# STM32F103C8T6_Core.net
KiCad netlist of a schematic drawn in Altium Designer
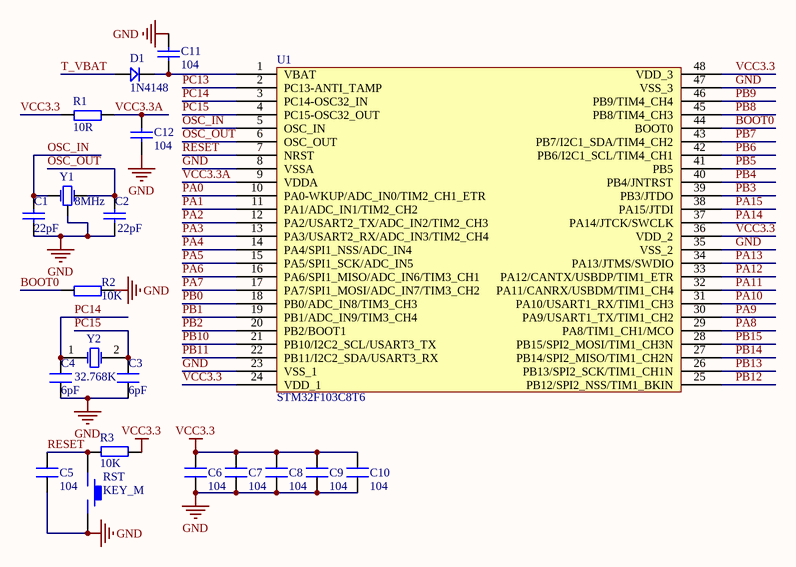
[diagram p0: STM32F103C8T6_Core.SchDoc]

(export (version "E")
  (design (tool "Eeschema 10.0.6"))
  (components
    (comp (ref "C1") (value "22pF") (footprint "C 0603_M") (libsource (lib "L476") (part "CAP")))
    (comp (ref "C2") (value "22pF") (footprint "C 0603_M") (libsource (lib "L476") (part "CAP")))
    (comp (ref "C3")
      (value "6pF")
      (footprint "C 0603_M")
      (libsource (lib "WarShip V3 STM32103封装库") (part "C"))
    )
    (comp (ref "C4")
      (value "6pF")
      (footprint "C 0603_M")
      (libsource (lib "WarShip V3 STM32103封装库") (part "C"))
    )
    (comp (ref "C5")
      (value "104")
      (footprint "C 0603_M")
      (libsource (lib "WarShip V3 STM32103封装库") (part "C"))
    )
    (comp (ref "C6")
      (value "104")
      (footprint "C 0603_M")
      (libsource (lib "WarShip V3 STM32103封装库") (part "C"))
    )
    (comp (ref "C7")
      (value "104")
      (footprint "C 0603_M")
      (libsource (lib "WarShip V3 STM32103封装库") (part "C"))
    )
    (comp (ref "C8")
      (value "104")
      (footprint "C 0603_M")
      (libsource (lib "WarShip V3 STM32103封装库") (part "C"))
    )
    (comp (ref "C9")
      (value "104")
      (footprint "C 0603_M")
      (libsource (lib "WarShip V3 STM32103封装库") (part "C"))
    )
    (comp (ref "C10")
      (value "104")
      (footprint "C 0603_M")
      (libsource (lib "WarShip V3 STM32103封装库") (part "C"))
    )
    (comp (ref "C11") (value "104") (footprint "C 0603_M") (libsource (lib "L476") (part "CAP")))
    (comp (ref "C12") (value "104") (footprint "C 0603_M") (libsource (lib "L476") (part "CAP")))
    (comp (ref "D1")
      (value "1N4148")
      (footprint "DIODE_SOP")
      (libsource (lib "阿波罗STM32F4&F7底板封装库") (part "D"))
    )
    (comp (ref "R1")
      (value "10R")
      (footprint "R 0603_M")
      (libsource (lib "WarShip V3 STM32103封装库") (part "R"))
    )
    (comp (ref "R2")
      (value "10K")
      (footprint "R 0603_M")
      (libsource (lib "WarShip V3 STM32103封装库") (part "R"))
    )
    (comp (ref "R3")
      (value "10K")
      (footprint "R 0603_M")
      (libsource (lib "WarShip V3 STM32103封装库") (part "R"))
    )
    (comp (ref "RST")
      (value "KEY_M")
      (footprint "TSW SMD-3*6*2.5")
      (libsource (lib "STM32F429核心板封装库") (part "KEY_M"))
    )
    (comp (ref "U1")
      (value "STM32F103C8T6")
      (footprint "LQFP-48PIN")
      (libsource (lib "Pandora_STM32L4_Board_V2.4") (part "U-STM32F103C8T6"))
    )
    (comp (ref "Y1")
      (value "8MHz")
      (footprint "Y-XTAL-3215-3P")
      (description "XTAL,3215,8MHz")
      (libsource (lib "Pandora_STM32L4_Board_V2.4") (part "Y-3215-8M"))
    )
    (comp (ref "Y2")
      (value "32.768K")
      (footprint "OSC 3215-2P")
      (description "Crystal Oscillator")
      (fields (field (name "PUBLISHER") "Altium Limited"))
      (libsource (lib "WarShip V3 STM32103封装库") (part "XTAL"))
    )
  )
  (nets
    (net (code "1") (name "/BOOT0") (class "Default")
      (node (ref "R2") (pin "1") (pintype "passive"))
      (node (ref "U1") (pin "44") (pinfunction "BOOT0_44") (pintype "passive"))
    )
    (net (code "2") (name "/OSC_IN") (class "Default")
      (node (ref "C1") (pin "2") (pinfunction "2_2") (pintype "passive"))
      (node (ref "U1") (pin "5") (pinfunction "OSC_IN_5") (pintype "passive"))
      (node (ref "Y1") (pin "1") (pinfunction "OSC1_1") (pintype "passive"))
    )
    (net (code "3") (name "/OSC_OUT") (class "Default")
      (node (ref "C2") (pin "2") (pinfunction "2_2") (pintype "passive"))
      (node (ref "U1") (pin "6") (pinfunction "OSC_OUT_6") (pintype "passive"))
      (node (ref "Y1") (pin "3") (pinfunction "OSC2_3") (pintype "passive"))
    )
    (net (code "4") (name "/PA0") (class "Default")
      (node (ref "U1") (pin "10") (pinfunction "PA0-WKUP/ADC_IN0/TIM2_CH1_ETR_10") (pintype "passive"))
    )
    (net (code "5") (name "/PA1") (class "Default")
      (node (ref "U1") (pin "11") (pinfunction "PA1/ADC_IN1/TIM2_CH2_11") (pintype "passive"))
    )
    (net (code "6") (name "/PA2") (class "Default")
      (node (ref "U1") (pin "12") (pinfunction "PA2/USART2_TX/ADC_IN2/TIM2_CH3_12") (pintype "passive"))
    )
    (net (code "7") (name "/PA3") (class "Default")
      (node (ref "U1") (pin "13") (pinfunction "PA3/USART2_RX/ADC_IN3/TIM2_CH4_13") (pintype "passive"))
    )
    (net (code "8") (name "/PA4") (class "Default")
      (node (ref "U1") (pin "14") (pinfunction "PA4/SPI1_NSS/ADC_IN4_14") (pintype "passive"))
    )
    (net (code "9") (name "/PA5") (class "Default")
      (node (ref "U1") (pin "15") (pinfunction "PA5/SPI1_SCK/ADC_IN5_15") (pintype "passive"))
    )
    (net (code "10") (name "/PA6") (class "Default")
      (node (ref "U1") (pin "16") (pinfunction "PA6/SPI1_MISO/ADC_IN6/TIM3_CH1_16") (pintype "passive"))
    )
    (net (code "11") (name "/PA7") (class "Default")
      (node (ref "U1") (pin "17") (pinfunction "PA7/SPI1_MOSI/ADC_IN7/TIM3_CH2_17") (pintype "passive"))
    )
    (net (code "12") (name "/PA8") (class "Default")
      (node (ref "U1") (pin "29") (pinfunction "PA8/TIM1_CH1/MCO_29") (pintype "passive"))
    )
    (net (code "13") (name "/PA9") (class "Default")
      (node (ref "U1") (pin "30") (pinfunction "PA9/USART1_TX/TIM1_CH2_30") (pintype "passive"))
    )
    (net (code "14") (name "/PA10") (class "Default")
      (node (ref "U1") (pin "31") (pinfunction "PA10/USART1_RX/TIM1_CH3_31") (pintype "passive"))
    )
    (net (code "15") (name "/PA11") (class "Default")
      (node (ref "U1") (pin "32") (pinfunction "PA11/CANRX/USBDM/TIM1_CH4_32") (pintype "passive"))
    )
    (net (code "16") (name "/PA12") (class "Default")
      (node (ref "U1") (pin "33") (pinfunction "PA12/CANTX/USBDP/TIM1_ETR_33") (pintype "passive"))
    )
    (net (code "17") (name "/PA13") (class "Default")
      (node (ref "U1") (pin "34") (pinfunction "PA13/JTMS/SWDIO_34") (pintype "passive"))
    )
    (net (code "18") (name "/PA14") (class "Default")
      (node (ref "U1") (pin "37") (pinfunction "PA14/JTCK/SWCLK_37") (pintype "passive"))
    )
    (net (code "19") (name "/PA15") (class "Default")
      (node (ref "U1") (pin "38") (pinfunction "PA15/JTDI_38") (pintype "passive"))
    )
    (net (code "20") (name "/PB0") (class "Default")
      (node (ref "U1") (pin "18") (pinfunction "PB0/ADC_IN8/TIM3_CH3_18") (pintype "passive"))
    )
    (net (code "21") (name "/PB1") (class "Default")
      (node (ref "U1") (pin "19") (pinfunction "PB1/ADC_IN9/TIM3_CH4_19") (pintype "passive"))
    )
    (net (code "22") (name "/PB2") (class "Default")
      (node (ref "U1") (pin "20") (pinfunction "PB2/BOOT1_20") (pintype "passive"))
    )
    (net (code "23") (name "/PB3") (class "Default")
      (node (ref "U1") (pin "39") (pinfunction "PB3/JTDO_39") (pintype "passive"))
    )
    (net (code "24") (name "/PB4") (class "Default")
      (node (ref "U1") (pin "40") (pinfunction "PB4/JNTRST_40") (pintype "passive"))
    )
    (net (code "25") (name "/PB5") (class "Default")
      (node (ref "U1") (pin "41") (pinfunction "PB5_41") (pintype "passive"))
    )
    (net (code "26") (name "/PB6") (class "Default")
      (node (ref "U1") (pin "42") (pinfunction "PB6/I2C1_SCL/TIM4_CH1_42") (pintype "passive"))
    )
    (net (code "27") (name "/PB7") (class "Default")
      (node (ref "U1") (pin "43") (pinfunction "PB7/I2C1_SDA/TIM4_CH2_43") (pintype "passive"))
    )
    (net (code "28") (name "/PB8") (class "Default")
      (node (ref "U1") (pin "45") (pinfunction "PB8/TIM4_CH3_45") (pintype "passive"))
    )
    (net (code "29") (name "/PB9") (class "Default")
      (node (ref "U1") (pin "46") (pinfunction "PB9/TIM4_CH4_46") (pintype "passive"))
    )
    (net (code "30") (name "/PB10") (class "Default")
      (node (ref "U1") (pin "21") (pinfunction "PB10/I2C2_SCL/USART3_TX_21") (pintype "passive"))
    )
    (net (code "31") (name "/PB11") (class "Default")
      (node (ref "U1") (pin "22") (pinfunction "PB11/I2C2_SDA/USART3_RX_22") (pintype "passive"))
    )
    (net (code "32") (name "/PB12") (class "Default")
      (node (ref "U1") (pin "25") (pinfunction "PB12/SPI2_NSS/TIM1_BKIN_25") (pintype "passive"))
    )
    (net (code "33") (name "/PB13") (class "Default")
      (node (ref "U1") (pin "26") (pinfunction "PB13/SPI2_SCK/TIM1_CH1N_26") (pintype "passive"))
    )
    (net (code "34") (name "/PB14") (class "Default")
      (node (ref "U1") (pin "27") (pinfunction "PB14/SPI2_MISO/TIM1_CH2N_27") (pintype "passive"))
    )
    (net (code "35") (name "/PB15") (class "Default")
      (node (ref "U1") (pin "28") (pinfunction "PB15/SPI2_MOSI/TIM1_CH3N_28") (pintype "passive"))
    )
    (net (code "36") (name "/PC13") (class "Default")
      (node (ref "U1") (pin "2") (pinfunction "PC13-ANTI_TAMP_2") (pintype "passive"))
    )
    (net (code "37") (name "/PC14") (class "Default")
      (node (ref "C4") (pin "2") (pintype "passive"))
      (node (ref "U1") (pin "3") (pinfunction "PC14-OSC32_IN_3") (pintype "passive"))
      (node (ref "Y2") (pin "1") (pinfunction "OSC1_1") (pintype "passive"))
    )
    (net (code "38") (name "/PC15") (class "Default")
      (node (ref "C3") (pin "2") (pintype "passive"))
      (node (ref "U1") (pin "4") (pinfunction "PC15-OSC32_OUT_4") (pintype "passive"))
      (node (ref "Y2") (pin "2") (pinfunction "OSC2_2") (pintype "passive"))
    )
    (net (code "39") (name "/RESET") (class "Default")
      (node (ref "C5") (pin "2") (pintype "passive"))
      (node (ref "R3") (pin "2") (pintype "passive"))
      (node (ref "RST") (pin "1") (pinfunction "1_1") (pintype "passive"))
      (node (ref "U1") (pin "7") (pinfunction "NRST_7") (pintype "passive"))
    )
    (net (code "40") (name "/T_VBAT") (class "Default") (node (ref "D1") (pin "1") (pintype "passive")))
    (net (code "41") (name "/VCC3.3A") (class "Default")
      (node (ref "C12") (pin "2") (pinfunction "2_2") (pintype "passive"))
      (node (ref "R1") (pin "2") (pintype "passive"))
      (node (ref "U1") (pin "9") (pinfunction "VDDA_9") (pintype "passive"))
    )
    (net (code "42") (name "GND") (class "Default")
      (node (ref "C1") (pin "1") (pinfunction "1_1") (pintype "passive"))
      (node (ref "C10") (pin "1") (pintype "passive"))
      (node (ref "C11") (pin "2") (pinfunction "2_2") (pintype "passive"))
      (node (ref "C12") (pin "1") (pinfunction "1_1") (pintype "passive"))
      (node (ref "C2") (pin "1") (pinfunction "1_1") (pintype "passive"))
      (node (ref "C3") (pin "1") (pintype "passive"))
      (node (ref "C4") (pin "1") (pintype "passive"))
      (node (ref "C5") (pin "1") (pintype "passive"))
      (node (ref "C6") (pin "1") (pintype "passive"))
      (node (ref "C7") (pin "1") (pintype "passive"))
      (node (ref "C8") (pin "1") (pintype "passive"))
      (node (ref "C9") (pin "1") (pintype "passive"))
      (node (ref "R2") (pin "2") (pintype "passive"))
      (node (ref "RST") (pin "2") (pinfunction "2_2") (pintype "passive"))
      (node (ref "U1") (pin "23") (pinfunction "VSS_1_23") (pintype "passive"))
      (node (ref "U1") (pin "35") (pinfunction "VSS_2_35") (pintype "passive"))
      (node (ref "U1") (pin "47") (pinfunction "VSS_3_47") (pintype "passive"))
      (node (ref "U1") (pin "8") (pinfunction "VSSA_8") (pintype "passive"))
      (node (ref "Y1") (pin "2") (pinfunction "GND_2") (pintype "passive"))
    )
    (net (code "43") (name "Net-(U1-VBAT)") (class "Default")
      (node (ref "C11") (pin "1") (pinfunction "1_1") (pintype "passive"))
      (node (ref "D1") (pin "2") (pintype "passive"))
      (node (ref "U1") (pin "1") (pinfunction "VBAT_1") (pintype "passive"))
    )
    (net (code "44") (name "VCC3.3") (class "Default")
      (node (ref "C10") (pin "2") (pintype "passive"))
      (node (ref "C6") (pin "2") (pintype "passive"))
      (node (ref "C7") (pin "2") (pintype "passive"))
      (node (ref "C8") (pin "2") (pintype "passive"))
      (node (ref "C9") (pin "2") (pintype "passive"))
      (node (ref "R1") (pin "1") (pintype "passive"))
      (node (ref "R3") (pin "1") (pintype "passive"))
      (node (ref "U1") (pin "24") (pinfunction "VDD_1_24") (pintype "passive"))
      (node (ref "U1") (pin "36") (pinfunction "VDD_2_36") (pintype "passive"))
      (node (ref "U1") (pin "48") (pinfunction "VDD_3_48") (pintype "passive"))
    )
  )
)
